# Interface_R1-0.net
KiCad netlist of a schematic drawn in EAGLE
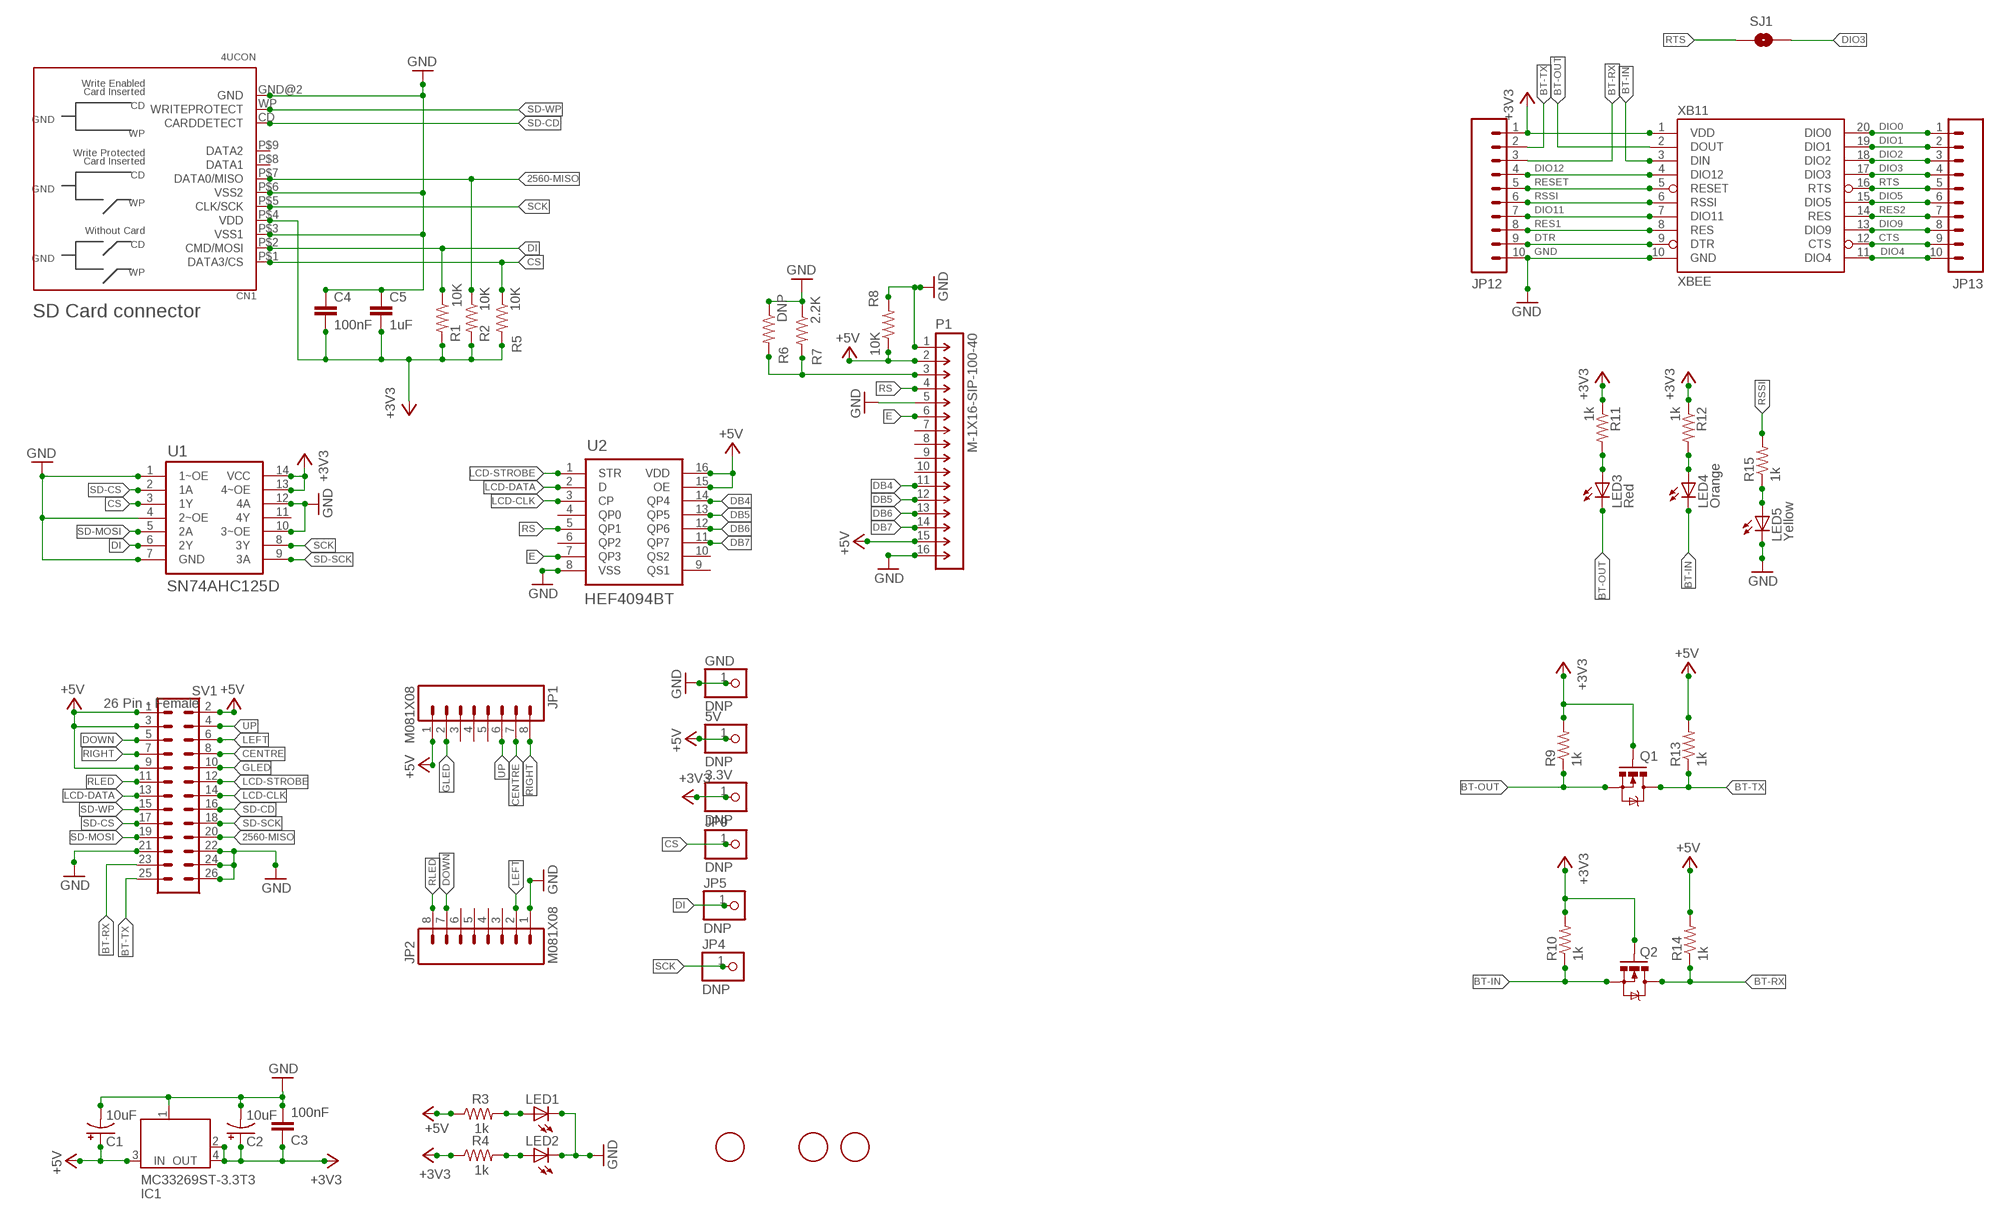
[diagram p0: schematic, sheet 1]

(export (version "E")
  (design (tool "Eeschema 10.0.6"))
  (components
    (comp (ref "3.3V")
      (value "DNP")
      (footprint "eagle-import:1X01")
      (libsource (lib "eagle-import") (part "PINHD-1X1"))
    )
    (comp (ref "5V")
      (value "DNP")
      (footprint "eagle-import:1X01")
      (libsource (lib "eagle-import") (part "PINHD-1X1"))
    )
    (comp (ref "C1")
      (value "10uF")
      (footprint "eagle-import:EIA3216")
      (libsource (lib "eagle-import") (part "CAP_POL1206"))
    )
    (comp (ref "C2")
      (value "10uF")
      (footprint "eagle-import:EIA3216")
      (libsource (lib "eagle-import") (part "CAP_POL1206"))
    )
    (comp (ref "C3")
      (value "100nF")
      (footprint "eagle-import:0805")
      (libsource (lib "eagle-import") (part "CAP0805"))
    )
    (comp (ref "C4")
      (value "100nF")
      (footprint "eagle-import:0805")
      (libsource (lib "eagle-import") (part "CAP0805"))
    )
    (comp (ref "C5")
      (value "1uF")
      (footprint "eagle-import:0805")
      (libsource (lib "eagle-import") (part "CAP0805"))
    )
    (comp (ref "CN1")
      (value "4UCON")
      (footprint "eagle-import:SDCARD_SMT_4U19646")
      (libsource (lib "eagle-import") (part "SDCARD19646"))
    )
    (comp (ref "GND")
      (value "DNP")
      (footprint "eagle-import:1X01")
      (libsource (lib "eagle-import") (part "PINHD-1X1"))
    )
    (comp (ref "IC1")
      (value "MC33269ST-3.3T3")
      (footprint "eagle-import:SOT223")
      (libsource (lib "eagle-import") (part "MC33269ST-3.3T3"))
    )
    (comp (ref "JP1")
      (value "M081X08")
      (footprint "eagle-import:1X08")
      (libsource (lib "eagle-import") (part "M081X08"))
    )
    (comp (ref "JP2")
      (value "M081X08")
      (footprint "eagle-import:1X08")
      (libsource (lib "eagle-import") (part "M081X08"))
    )
    (comp (ref "JP3")
      (value "FIDUCIAL1.5X3")
      (footprint "eagle-import:FIDUCIAL-1.5X3")
      (libsource (lib "eagle-import") (part "FIDUCIAL1.5X3"))
    )
    (comp (ref "JP4")
      (value "DNP")
      (footprint "eagle-import:1X01")
      (libsource (lib "eagle-import") (part "PINHD-1X1"))
    )
    (comp (ref "JP5")
      (value "DNP")
      (footprint "eagle-import:1X01")
      (libsource (lib "eagle-import") (part "PINHD-1X1"))
    )
    (comp (ref "JP9")
      (value "DNP")
      (footprint "eagle-import:1X01")
      (libsource (lib "eagle-import") (part "PINHD-1X1"))
    )
    (comp (ref "JP10")
      (value "FIDUCIAL1.5X3")
      (footprint "eagle-import:FIDUCIAL-1.5X3")
      (libsource (lib "eagle-import") (part "FIDUCIAL1.5X3"))
    )
    (comp (ref "JP11")
      (value "FIDUCIAL1.5X3")
      (footprint "eagle-import:FIDUCIAL-1.5X3")
      (libsource (lib "eagle-import") (part "FIDUCIAL1.5X3"))
    )
    (comp (ref "JP12")
      (value "M100.1")
      (footprint "eagle-import:1X10")
      (libsource (lib "eagle-import") (part "M100.1"))
    )
    (comp (ref "JP13")
      (value "M100.1")
      (footprint "eagle-import:1X10")
      (libsource (lib "eagle-import") (part "M100.1"))
    )
    (comp (ref "LED1")
      (value "GREEN")
      (footprint "eagle-import:LED-0805")
      (libsource (lib "eagle-import") (part "LED0805"))
    )
    (comp (ref "LED2")
      (value "Blue")
      (footprint "eagle-import:LED-0805")
      (libsource (lib "eagle-import") (part "LED0805"))
    )
    (comp (ref "LED3")
      (value "Red")
      (footprint "eagle-import:LED-0805")
      (libsource (lib "eagle-import") (part "LED0805"))
    )
    (comp (ref "LED4")
      (value "Orange")
      (footprint "eagle-import:LED-0805")
      (libsource (lib "eagle-import") (part "LED0805"))
    )
    (comp (ref "LED5")
      (value "Yellow")
      (footprint "eagle-import:LED-0805")
      (libsource (lib "eagle-import") (part "LED0805"))
    )
    (comp (ref "P1")
      (value "M-1X16-SIP-100-40")
      (footprint "eagle-import:SIP-100-16-40")
      (libsource (lib "eagle-import") (part "M-1X16-SIP-100-40"))
    )
    (comp (ref "Q1")
      (value "MOSFET-NCHANNELSMD")
      (footprint "eagle-import:SOT23-3")
      (libsource (lib "eagle-import") (part "MOSFET-NCHANNELSMD"))
    )
    (comp (ref "Q2")
      (value "MOSFET-NCHANNELSMD")
      (footprint "eagle-import:SOT23-3")
      (libsource (lib "eagle-import") (part "MOSFET-NCHANNELSMD"))
    )
    (comp (ref "R1")
      (value "10K")
      (footprint "eagle-import:0805")
      (libsource (lib "eagle-import") (part "RESISTOR"))
    )
    (comp (ref "R2")
      (value "10K")
      (footprint "eagle-import:0805")
      (libsource (lib "eagle-import") (part "RESISTOR"))
    )
    (comp (ref "R3")
      (value "1k")
      (footprint "eagle-import:0805")
      (libsource (lib "eagle-import") (part "RESISTOR"))
    )
    (comp (ref "R4")
      (value "1k")
      (footprint "eagle-import:0805")
      (libsource (lib "eagle-import") (part "RESISTOR"))
    )
    (comp (ref "R5")
      (value "10K")
      (footprint "eagle-import:0805")
      (libsource (lib "eagle-import") (part "RESISTOR"))
    )
    (comp (ref "R6")
      (value "DNP")
      (footprint "eagle-import:0805")
      (libsource (lib "eagle-import") (part "RESISTOR"))
    )
    (comp (ref "R7")
      (value "2.2K")
      (footprint "eagle-import:0805")
      (libsource (lib "eagle-import") (part "RESISTOR"))
    )
    (comp (ref "R8")
      (value "10K")
      (footprint "eagle-import:0805")
      (libsource (lib "eagle-import") (part "RESISTOR"))
    )
    (comp (ref "R9")
      (value "1k")
      (footprint "eagle-import:0805")
      (libsource (lib "eagle-import") (part "RESISTOR"))
    )
    (comp (ref "R10")
      (value "1k")
      (footprint "eagle-import:0805")
      (libsource (lib "eagle-import") (part "RESISTOR"))
    )
    (comp (ref "R11")
      (value "1k")
      (footprint "eagle-import:0805")
      (libsource (lib "eagle-import") (part "RESISTOR"))
    )
    (comp (ref "R12")
      (value "1k")
      (footprint "eagle-import:0805")
      (libsource (lib "eagle-import") (part "RESISTOR"))
    )
    (comp (ref "R13")
      (value "1k")
      (footprint "eagle-import:0805")
      (libsource (lib "eagle-import") (part "RESISTOR"))
    )
    (comp (ref "R14")
      (value "1k")
      (footprint "eagle-import:0805")
      (libsource (lib "eagle-import") (part "RESISTOR"))
    )
    (comp (ref "R15")
      (value "1k")
      (footprint "eagle-import:0805")
      (libsource (lib "eagle-import") (part "RESISTOR"))
    )
    (comp (ref "SJ1")
      (value "SOLDERJUMPERNO")
      (footprint "eagle-import:SJ_2S-NO")
      (libsource (lib "eagle-import") (part "SOLDERJUMPERNO"))
    )
    (comp (ref "SV1")
      (value "26 Pin - Female")
      (footprint "eagle-import:ML26")
      (libsource (lib "eagle-import") (part "ML26"))
    )
    (comp (ref "U1")
      (value "SN74AHC125D")
      (footprint "eagle-import:SOIC127P600X175-14N")
      (libsource (lib "eagle-import") (part "SN74AHC125D"))
    )
    (comp (ref "U2")
      (value "HEF4094BT")
      (footprint "eagle-import:SOIC127P600X175-16N")
      (fields (field (name "MPN") "HHEF4094BT"))
      (libsource (lib "eagle-import") (part "HEF4094BT"))
    )
    (comp (ref "XB11")
      (value "XBEE")
      (footprint "eagle-import:XBEE-SILK")
      (libsource (lib "eagle-import") (part "XBEE-1B2"))
    )
  )
  (nets
    (net (code "1") (name "+3V3") (class "Default")
      (node (ref "3.3V") (pin "1") (pinfunction "1_1") (pintype "passive"))
      (node (ref "C2") (pin "A") (pinfunction "+_A") (pintype "passive"))
      (node (ref "C3") (pin "1") (pinfunction "1_1") (pintype "passive"))
      (node (ref "C4") (pin "2") (pinfunction "2_2") (pintype "passive"))
      (node (ref "C5") (pin "2") (pinfunction "2_2") (pintype "passive"))
      (node (ref "CN1") (pin "P$4") (pinfunction "VDD_P$4") (pintype "bidirectional"))
      (node (ref "IC1") (pin "2") (pinfunction "OUT_2") (pintype "passive"))
      (node (ref "IC1") (pin "4") (pinfunction "OUT_4") (pintype "passive"))
      (node (ref "JP12") (pin "1") (pinfunction "1_1") (pintype "passive"))
      (node (ref "Q1") (pin "1") (pinfunction "G_1") (pintype "passive"))
      (node (ref "Q2") (pin "1") (pinfunction "G_1") (pintype "passive"))
      (node (ref "R1") (pin "2") (pinfunction "2_2") (pintype "passive"))
      (node (ref "R10") (pin "2") (pinfunction "2_2") (pintype "passive"))
      (node (ref "R11") (pin "1") (pinfunction "1_1") (pintype "passive"))
      (node (ref "R12") (pin "1") (pinfunction "1_1") (pintype "passive"))
      (node (ref "R2") (pin "2") (pinfunction "2_2") (pintype "passive"))
      (node (ref "R4") (pin "1") (pinfunction "1_1") (pintype "passive"))
      (node (ref "R5") (pin "2") (pinfunction "2_2") (pintype "passive"))
      (node (ref "R9") (pin "2") (pinfunction "2_2") (pintype "passive"))
      (node (ref "U1") (pin "13") (pinfunction "4~{OE}_13") (pintype "input"))
      (node (ref "U1") (pin "14") (pinfunction "VCC_14") (pintype "power_in"))
      (node (ref "XB11") (pin "1") (pinfunction "VDD_1") (pintype "power_in"))
    )
    (net (code "2") (name "+5V") (class "Default")
      (node (ref "5V") (pin "1") (pinfunction "1_1") (pintype "passive"))
      (node (ref "C1") (pin "A") (pinfunction "+_A") (pintype "passive"))
      (node (ref "IC1") (pin "3") (pinfunction "IN_3") (pintype "input"))
      (node (ref "JP1") (pin "1") (pinfunction "1_1") (pintype "passive"))
      (node (ref "P1") (pin "15") (pinfunction "15_15") (pintype "passive"))
      (node (ref "P1") (pin "2") (pinfunction "2_2") (pintype "passive"))
      (node (ref "R13") (pin "2") (pinfunction "2_2") (pintype "passive"))
      (node (ref "R14") (pin "2") (pinfunction "2_2") (pintype "passive"))
      (node (ref "R3") (pin "1") (pinfunction "1_1") (pintype "passive"))
      (node (ref "R8") (pin "1") (pinfunction "1_1") (pintype "passive"))
      (node (ref "SV1") (pin "1") (pinfunction "1_1") (pintype "passive"))
      (node (ref "SV1") (pin "2") (pinfunction "2_2") (pintype "passive"))
      (node (ref "SV1") (pin "3") (pinfunction "3_3") (pintype "passive"))
      (node (ref "SV1") (pin "9") (pinfunction "9_9") (pintype "passive"))
      (node (ref "U2") (pin "15") (pinfunction "OE_15") (pintype "input"))
      (node (ref "U2") (pin "16") (pinfunction "VDD_16") (pintype "power_in"))
    )
    (net (code "3") (name "/CTS") (class "Default")
      (node (ref "JP13") (pin "9") (pinfunction "9_9") (pintype "passive"))
      (node (ref "XB11") (pin "12") (pinfunction "CTS_12") (pintype "output"))
    )
    (net (code "4") (name "/DIO0") (class "Default")
      (node (ref "JP13") (pin "1") (pinfunction "1_1") (pintype "passive"))
      (node (ref "XB11") (pin "20") (pinfunction "DIO0_20") (pintype "bidirectional"))
    )
    (net (code "5") (name "/DIO1") (class "Default")
      (node (ref "JP13") (pin "2") (pinfunction "2_2") (pintype "passive"))
      (node (ref "XB11") (pin "19") (pinfunction "DIO1_19") (pintype "bidirectional"))
    )
    (net (code "6") (name "/DIO2") (class "Default")
      (node (ref "JP13") (pin "3") (pinfunction "3_3") (pintype "passive"))
      (node (ref "XB11") (pin "18") (pinfunction "DIO2_18") (pintype "bidirectional"))
    )
    (net (code "7") (name "/DIO4") (class "Default")
      (node (ref "JP13") (pin "10") (pinfunction "10_10") (pintype "passive"))
      (node (ref "XB11") (pin "11") (pinfunction "DIO4_11") (pintype "bidirectional"))
    )
    (net (code "8") (name "/DIO5") (class "Default")
      (node (ref "JP13") (pin "6") (pinfunction "6_6") (pintype "passive"))
      (node (ref "XB11") (pin "15") (pinfunction "DIO5_15") (pintype "bidirectional"))
    )
    (net (code "9") (name "/DIO9") (class "Default")
      (node (ref "JP13") (pin "8") (pinfunction "8_8") (pintype "passive"))
      (node (ref "XB11") (pin "13") (pinfunction "DIO9_13") (pintype "bidirectional"))
    )
    (net (code "10") (name "/DIO11") (class "Default")
      (node (ref "JP12") (pin "7") (pinfunction "7_7") (pintype "passive"))
      (node (ref "XB11") (pin "7") (pinfunction "DIO11_7") (pintype "bidirectional"))
    )
    (net (code "11") (name "/DIO12") (class "Default")
      (node (ref "JP12") (pin "4") (pinfunction "4_4") (pintype "passive"))
      (node (ref "XB11") (pin "4") (pinfunction "DIO12_4") (pintype "bidirectional"))
    )
    (net (code "12") (name "/DTR") (class "Default")
      (node (ref "JP12") (pin "9") (pinfunction "9_9") (pintype "passive"))
      (node (ref "XB11") (pin "9") (pinfunction "DTR_9") (pintype "bidirectional"))
    )
    (net (code "13") (name "/RES1") (class "Default")
      (node (ref "JP12") (pin "8") (pinfunction "8_8") (pintype "passive"))
      (node (ref "XB11") (pin "8") (pinfunction "RES_8") (pintype "bidirectional"))
    )
    (net (code "14") (name "/RES2") (class "Default")
      (node (ref "JP13") (pin "7") (pinfunction "7_7") (pintype "passive"))
      (node (ref "XB11") (pin "14") (pinfunction "RES_14") (pintype "bidirectional"))
    )
    (net (code "15") (name "/RESET") (class "Default")
      (node (ref "JP12") (pin "5") (pinfunction "5_5") (pintype "passive"))
      (node (ref "XB11") (pin "5") (pinfunction "RESET_5") (pintype "input"))
    )
    (net (code "16") (name "2560-MISO") (class "Default")
      (node (ref "CN1") (pin "P$7") (pinfunction "DATA0/MISO_P$7") (pintype "bidirectional"))
      (node (ref "R2") (pin "1") (pinfunction "1_1") (pintype "passive"))
      (node (ref "SV1") (pin "20") (pinfunction "20_20") (pintype "passive"))
    )
    (net (code "17") (name "BT-IN") (class "Default")
      (node (ref "LED4") (pin "C") (pinfunction "C_C") (pintype "passive"))
      (node (ref "Q2") (pin "2") (pinfunction "S_2") (pintype "passive"))
      (node (ref "R10") (pin "1") (pinfunction "1_1") (pintype "passive"))
      (node (ref "XB11") (pin "3") (pinfunction "DIN_3") (pintype "input"))
    )
    (net (code "18") (name "BT-OUT") (class "Default")
      (node (ref "LED3") (pin "C") (pinfunction "C_C") (pintype "passive"))
      (node (ref "Q1") (pin "2") (pinfunction "S_2") (pintype "passive"))
      (node (ref "R9") (pin "1") (pinfunction "1_1") (pintype "passive"))
      (node (ref "XB11") (pin "2") (pinfunction "DOUT_2") (pintype "output"))
    )
    (net (code "19") (name "BT-RX") (class "Default")
      (node (ref "JP12") (pin "3") (pinfunction "3_3") (pintype "passive"))
      (node (ref "Q2") (pin "3") (pinfunction "D_3") (pintype "passive"))
      (node (ref "R14") (pin "1") (pinfunction "1_1") (pintype "passive"))
      (node (ref "SV1") (pin "23") (pinfunction "23_23") (pintype "passive"))
    )
    (net (code "20") (name "BT-TX") (class "Default")
      (node (ref "JP12") (pin "2") (pinfunction "2_2") (pintype "passive"))
      (node (ref "Q1") (pin "3") (pinfunction "D_3") (pintype "passive"))
      (node (ref "R13") (pin "1") (pinfunction "1_1") (pintype "passive"))
      (node (ref "SV1") (pin "25") (pinfunction "25_25") (pintype "passive"))
    )
    (net (code "21") (name "CENTRE") (class "Default")
      (node (ref "JP1") (pin "7") (pinfunction "7_7") (pintype "passive"))
      (node (ref "SV1") (pin "8") (pinfunction "8_8") (pintype "passive"))
    )
    (net (code "22") (name "CS") (class "Default")
      (node (ref "CN1") (pin "P$1") (pinfunction "DATA3/CS_P$1") (pintype "bidirectional"))
      (node (ref "JP9") (pin "1") (pinfunction "1_1") (pintype "passive"))
      (node (ref "R5") (pin "1") (pinfunction "1_1") (pintype "passive"))
      (node (ref "U1") (pin "3") (pinfunction "1Y_3") (pintype "output"))
    )
    (net (code "23") (name "DB4") (class "Default")
      (node (ref "P1") (pin "11") (pinfunction "11_11") (pintype "passive"))
      (node (ref "U2") (pin "14") (pinfunction "QP4_14") (pintype "output"))
    )
    (net (code "24") (name "DB5") (class "Default")
      (node (ref "P1") (pin "12") (pinfunction "12_12") (pintype "passive"))
      (node (ref "U2") (pin "13") (pinfunction "QP5_13") (pintype "output"))
    )
    (net (code "25") (name "DB6") (class "Default")
      (node (ref "P1") (pin "13") (pinfunction "13_13") (pintype "passive"))
      (node (ref "U2") (pin "12") (pinfunction "QP6_12") (pintype "output"))
    )
    (net (code "26") (name "DB7") (class "Default")
      (node (ref "P1") (pin "14") (pinfunction "14_14") (pintype "passive"))
      (node (ref "U2") (pin "11") (pinfunction "QP7_11") (pintype "output"))
    )
    (net (code "27") (name "DI") (class "Default")
      (node (ref "CN1") (pin "P$2") (pinfunction "CMD/MOSI_P$2") (pintype "bidirectional"))
      (node (ref "JP5") (pin "1") (pinfunction "1_1") (pintype "passive"))
      (node (ref "R1") (pin "1") (pinfunction "1_1") (pintype "passive"))
      (node (ref "U1") (pin "6") (pinfunction "2Y_6") (pintype "output"))
    )
    (net (code "28") (name "DIO3") (class "Default")
      (node (ref "JP13") (pin "4") (pinfunction "4_4") (pintype "passive"))
      (node (ref "SJ1") (pin "2") (pinfunction "2_2") (pintype "passive"))
      (node (ref "XB11") (pin "17") (pinfunction "DIO3_17") (pintype "bidirectional"))
    )
    (net (code "29") (name "DOWN") (class "Default")
      (node (ref "JP2") (pin "7") (pinfunction "7_7") (pintype "passive"))
      (node (ref "SV1") (pin "5") (pinfunction "5_5") (pintype "passive"))
    )
    (net (code "30") (name "E") (class "Default")
      (node (ref "P1") (pin "6") (pinfunction "6_6") (pintype "passive"))
      (node (ref "U2") (pin "7") (pinfunction "QP3_7") (pintype "output"))
    )
    (net (code "31") (name "GLED") (class "Default")
      (node (ref "JP1") (pin "2") (pinfunction "2_2") (pintype "passive"))
      (node (ref "SV1") (pin "10") (pinfunction "10_10") (pintype "passive"))
    )
    (net (code "32") (name "GND") (class "Default")
      (node (ref "C1") (pin "C") (pinfunction "-_C") (pintype "passive"))
      (node (ref "C2") (pin "C") (pinfunction "-_C") (pintype "passive"))
      (node (ref "C3") (pin "2") (pinfunction "2_2") (pintype "passive"))
      (node (ref "C4") (pin "1") (pinfunction "1_1") (pintype "passive"))
      (node (ref "C5") (pin "1") (pinfunction "1_1") (pintype "passive"))
      (node (ref "CN1") (pin "GND@2") (pinfunction "GND_GND@2") (pintype "bidirectional"))
      (node (ref "CN1") (pin "P$3") (pinfunction "VSS1_P$3") (pintype "bidirectional"))
      (node (ref "CN1") (pin "P$6") (pinfunction "VSS2_P$6") (pintype "bidirectional"))
      (node (ref "GND") (pin "1") (pinfunction "1_1") (pintype "passive"))
      (node (ref "IC1") (pin "1") (pinfunction "GND/ADJ_1") (pintype "input"))
      (node (ref "JP12") (pin "10") (pinfunction "10_10") (pintype "passive"))
      (node (ref "JP2") (pin "1") (pinfunction "1_1") (pintype "passive"))
      (node (ref "LED1") (pin "C") (pinfunction "C_C") (pintype "passive"))
      (node (ref "LED2") (pin "C") (pinfunction "C_C") (pintype "passive"))
      (node (ref "LED5") (pin "C") (pinfunction "C_C") (pintype "passive"))
      (node (ref "P1") (pin "1") (pinfunction "1_1") (pintype "passive"))
      (node (ref "P1") (pin "16") (pinfunction "16_16") (pintype "passive"))
      (node (ref "P1") (pin "5") (pinfunction "5_5") (pintype "passive"))
      (node (ref "R6") (pin "1") (pinfunction "1_1") (pintype "passive"))
      (node (ref "R7") (pin "1") (pinfunction "1_1") (pintype "passive"))
      (node (ref "R8") (pin "2") (pinfunction "2_2") (pintype "passive"))
      (node (ref "SV1") (pin "21") (pinfunction "21_21") (pintype "passive"))
      (node (ref "SV1") (pin "22") (pinfunction "22_22") (pintype "passive"))
      (node (ref "SV1") (pin "24") (pinfunction "24_24") (pintype "passive"))
      (node (ref "SV1") (pin "26") (pinfunction "26_26") (pintype "passive"))
      (node (ref "U1") (pin "1") (pinfunction "1~{OE}_1") (pintype "input"))
      (node (ref "U1") (pin "10") (pinfunction "3~{OE}_10") (pintype "input"))
      (node (ref "U1") (pin "12") (pinfunction "4A_12") (pintype "input"))
      (node (ref "U1") (pin "4") (pinfunction "2~{OE}_4") (pintype "input"))
      (node (ref "U1") (pin "7") (pinfunction "GND_7") (pintype "passive"))
      (node (ref "U2") (pin "8") (pinfunction "VSS_8") (pintype "power_in"))
      (node (ref "XB11") (pin "10") (pinfunction "GND_10") (pintype "power_in"))
    )
    (net (code "33") (name "LCD-CLK") (class "Default")
      (node (ref "SV1") (pin "14") (pinfunction "14_14") (pintype "passive"))
      (node (ref "U2") (pin "3") (pinfunction "CP_3") (pintype "input"))
    )
    (net (code "34") (name "LCD-DATA") (class "Default")
      (node (ref "SV1") (pin "13") (pinfunction "13_13") (pintype "passive"))
      (node (ref "U2") (pin "2") (pinfunction "D_2") (pintype "input"))
    )
    (net (code "35") (name "LCD-STROBE") (class "Default")
      (node (ref "SV1") (pin "12") (pinfunction "12_12") (pintype "passive"))
      (node (ref "U2") (pin "1") (pinfunction "STR_1") (pintype "input"))
    )
    (net (code "36") (name "LEFT") (class "Default")
      (node (ref "JP2") (pin "2") (pinfunction "2_2") (pintype "passive"))
      (node (ref "SV1") (pin "6") (pinfunction "6_6") (pintype "passive"))
    )
    (net (code "37") (name "Net-(LED1-PadA)") (class "Default")
      (node (ref "LED1") (pin "A") (pinfunction "A_A") (pintype "passive"))
      (node (ref "R3") (pin "2") (pinfunction "2_2") (pintype "passive"))
    )
    (net (code "38") (name "Net-(LED2-PadA)") (class "Default")
      (node (ref "LED2") (pin "A") (pinfunction "A_A") (pintype "passive"))
      (node (ref "R4") (pin "2") (pinfunction "2_2") (pintype "passive"))
    )
    (net (code "39") (name "Net-(LED3-PadA)") (class "Default")
      (node (ref "LED3") (pin "A") (pinfunction "A_A") (pintype "passive"))
      (node (ref "R11") (pin "2") (pinfunction "2_2") (pintype "passive"))
    )
    (net (code "40") (name "Net-(LED4-PadA)") (class "Default")
      (node (ref "LED4") (pin "A") (pinfunction "A_A") (pintype "passive"))
      (node (ref "R12") (pin "2") (pinfunction "2_2") (pintype "passive"))
    )
    (net (code "41") (name "Net-(LED5-PadA)") (class "Default")
      (node (ref "LED5") (pin "A") (pinfunction "A_A") (pintype "passive"))
      (node (ref "R15") (pin "1") (pinfunction "1_1") (pintype "passive"))
    )
    (net (code "42") (name "Net-(P1-Pad3)") (class "Default")
      (node (ref "P1") (pin "3") (pinfunction "3_3") (pintype "passive"))
      (node (ref "R6") (pin "2") (pinfunction "2_2") (pintype "passive"))
      (node (ref "R7") (pin "2") (pinfunction "2_2") (pintype "passive"))
    )
    (net (code "43") (name "RIGHT") (class "Default")
      (node (ref "JP1") (pin "8") (pinfunction "8_8") (pintype "passive"))
      (node (ref "SV1") (pin "7") (pinfunction "7_7") (pintype "passive"))
    )
    (net (code "44") (name "RLED") (class "Default")
      (node (ref "JP2") (pin "8") (pinfunction "8_8") (pintype "passive"))
      (node (ref "SV1") (pin "11") (pinfunction "11_11") (pintype "passive"))
    )
    (net (code "45") (name "RS") (class "Default")
      (node (ref "P1") (pin "4") (pinfunction "4_4") (pintype "passive"))
      (node (ref "U2") (pin "5") (pinfunction "QP1_5") (pintype "output"))
    )
    (net (code "46") (name "RSSI") (class "Default")
      (node (ref "JP12") (pin "6") (pinfunction "6_6") (pintype "passive"))
      (node (ref "R15") (pin "2") (pinfunction "2_2") (pintype "passive"))
      (node (ref "XB11") (pin "6") (pinfunction "RSSI_6") (pintype "bidirectional"))
    )
    (net (code "47") (name "RTS") (class "Default")
      (node (ref "JP13") (pin "5") (pinfunction "5_5") (pintype "passive"))
      (node (ref "SJ1") (pin "1") (pinfunction "1_1") (pintype "passive"))
      (node (ref "XB11") (pin "16") (pinfunction "RTS_16") (pintype "input"))
    )
    (net (code "48") (name "SCK") (class "Default")
      (node (ref "CN1") (pin "P$5") (pinfunction "CLK/SCK_P$5") (pintype "bidirectional"))
      (node (ref "JP4") (pin "1") (pinfunction "1_1") (pintype "passive"))
      (node (ref "U1") (pin "8") (pinfunction "3Y_8") (pintype "output"))
    )
    (net (code "49") (name "SD-CD") (class "Default")
      (node (ref "CN1") (pin "CD") (pinfunction "CARDDETECT_CD") (pintype "bidirectional"))
      (node (ref "SV1") (pin "16") (pinfunction "16_16") (pintype "passive"))
    )
    (net (code "50") (name "SD-CS") (class "Default")
      (node (ref "SV1") (pin "17") (pinfunction "17_17") (pintype "passive"))
      (node (ref "U1") (pin "2") (pinfunction "1A_2") (pintype "input"))
    )
    (net (code "51") (name "SD-MOSI") (class "Default")
      (node (ref "SV1") (pin "19") (pinfunction "19_19") (pintype "passive"))
      (node (ref "U1") (pin "5") (pinfunction "2A_5") (pintype "input"))
    )
    (net (code "52") (name "SD-SCK") (class "Default")
      (node (ref "SV1") (pin "18") (pinfunction "18_18") (pintype "passive"))
      (node (ref "U1") (pin "9") (pinfunction "3A_9") (pintype "input"))
    )
    (net (code "53") (name "SD-WP") (class "Default")
      (node (ref "CN1") (pin "WP") (pinfunction "WRITEPROTECT_WP") (pintype "bidirectional"))
      (node (ref "SV1") (pin "15") (pinfunction "15_15") (pintype "passive"))
    )
    (net (code "54") (name "UP") (class "Default")
      (node (ref "JP1") (pin "6") (pinfunction "6_6") (pintype "passive"))
      (node (ref "SV1") (pin "4") (pinfunction "4_4") (pintype "passive"))
    )
    (net (code "55") (name "unconnected-(CN1-DATA1-PadP$8)") (class "Default")
      (node (ref "CN1") (pin "P$8") (pinfunction "DATA1_P$8") (pintype "bidirectional"))
    )
    (net (code "56") (name "unconnected-(CN1-DATA2-PadP$9)") (class "Default")
      (node (ref "CN1") (pin "P$9") (pinfunction "DATA2_P$9") (pintype "bidirectional"))
    )
    (net (code "57") (name "unconnected-(JP1-Pad3)") (class "Default")
      (node (ref "JP1") (pin "3") (pinfunction "3_3") (pintype "passive"))
    )
    (net (code "58") (name "unconnected-(JP1-Pad4)") (class "Default")
      (node (ref "JP1") (pin "4") (pinfunction "4_4") (pintype "passive"))
    )
    (net (code "59") (name "unconnected-(JP1-Pad5)") (class "Default")
      (node (ref "JP1") (pin "5") (pinfunction "5_5") (pintype "passive"))
    )
    (net (code "60") (name "unconnected-(JP2-Pad3)") (class "Default")
      (node (ref "JP2") (pin "3") (pinfunction "3_3") (pintype "passive"))
    )
    (net (code "61") (name "unconnected-(JP2-Pad4)") (class "Default")
      (node (ref "JP2") (pin "4") (pinfunction "4_4") (pintype "passive"))
    )
    (net (code "62") (name "unconnected-(JP2-Pad5)") (class "Default")
      (node (ref "JP2") (pin "5") (pinfunction "5_5") (pintype "passive"))
    )
    (net (code "63") (name "unconnected-(JP2-Pad6)") (class "Default")
      (node (ref "JP2") (pin "6") (pinfunction "6_6") (pintype "passive"))
    )
    (net (code "64") (name "unconnected-(P1-Pad7)") (class "Default")
      (node (ref "P1") (pin "7") (pinfunction "7_7") (pintype "passive"))
    )
    (net (code "65") (name "unconnected-(P1-Pad8)") (class "Default")
      (node (ref "P1") (pin "8") (pinfunction "8_8") (pintype "passive"))
    )
    (net (code "66") (name "unconnected-(P1-Pad9)") (class "Default")
      (node (ref "P1") (pin "9") (pinfunction "9_9") (pintype "passive"))
    )
    (net (code "67") (name "unconnected-(P1-Pad10)") (class "Default")
      (node (ref "P1") (pin "10") (pinfunction "10_10") (pintype "passive"))
    )
    (net (code "68") (name "unconnected-(U1-4Y-Pad11)") (class "Default")
      (node (ref "U1") (pin "11") (pinfunction "4Y_11") (pintype "output"))
    )
    (net (code "69") (name "unconnected-(U2-QP0-Pad4)") (class "Default")
      (node (ref "U2") (pin "4") (pinfunction "QP0_4") (pintype "output"))
    )
    (net (code "70") (name "unconnected-(U2-QP2-Pad6)") (class "Default")
      (node (ref "U2") (pin "6") (pinfunction "QP2_6") (pintype "output"))
    )
    (net (code "71") (name "unconnected-(U2-QS1-Pad9)") (class "Default")
      (node (ref "U2") (pin "9") (pinfunction "QS1_9") (pintype "output"))
    )
    (net (code "72") (name "unconnected-(U2-QS2-Pad10)") (class "Default")
      (node (ref "U2") (pin "10") (pinfunction "QS2_10") (pintype "output"))
    )
  )
)
